# Schematic.net
KiCad netlist of a schematic drawn in Altium Designer
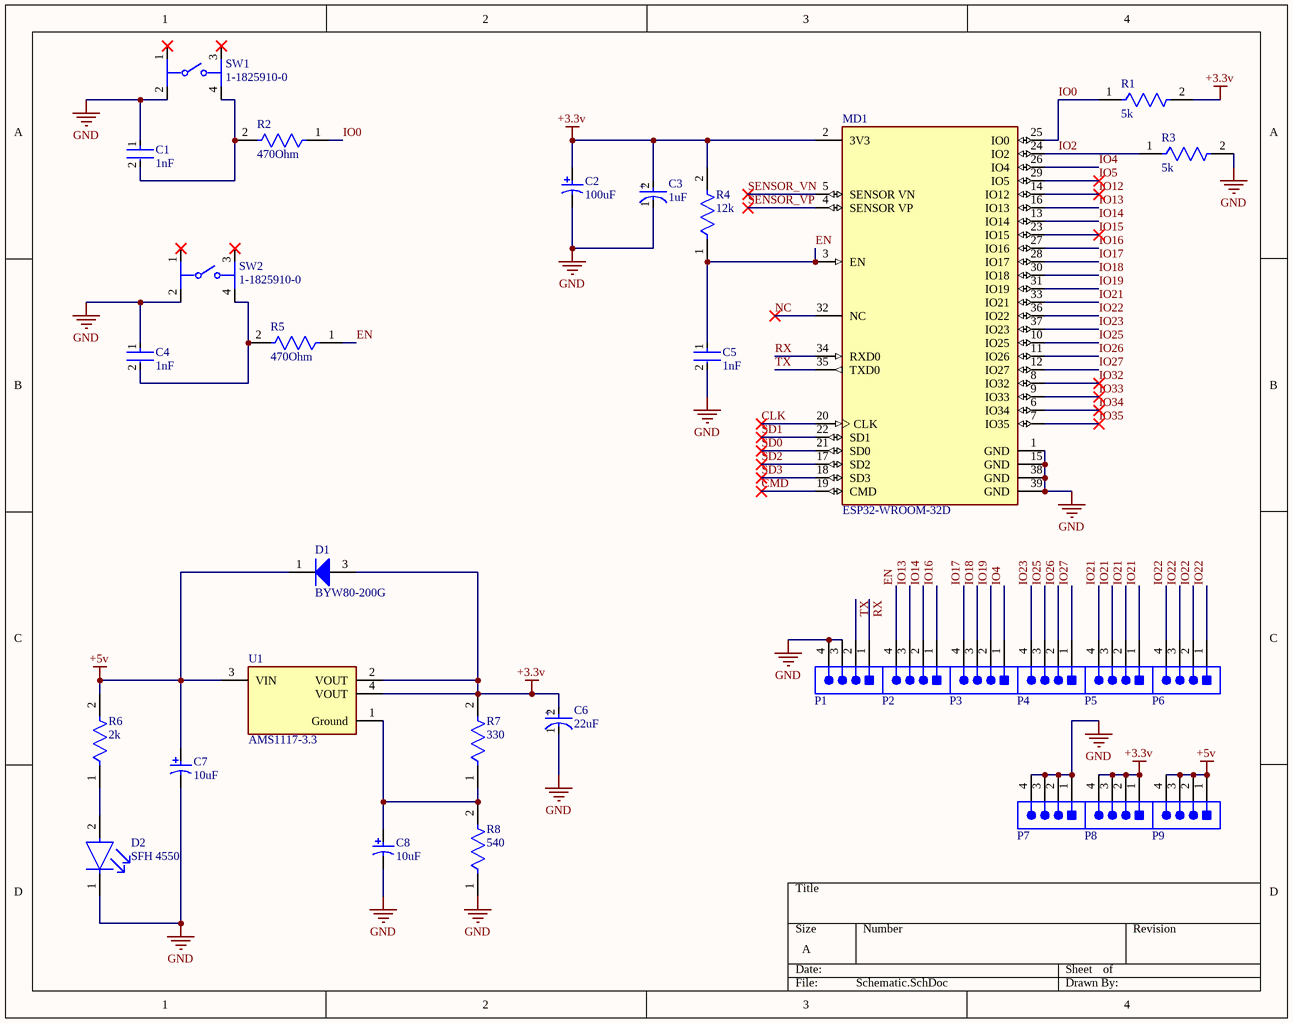
[diagram p0: Schematic.SchDoc]

(export (version "E")
  (design (tool "Eeschema 10.0.6"))
  (components
    (comp (ref "C1")
      (value "1nF")
      (footprint "FP-VY2102M29Y5US6TV7-MFG")
      (fields (field (name "VOLTAGE") "300V") (field (name "TOLERANCE") "20%"))
      (libsource (lib "Altium Content Vault") (part "11868f565c42a9108669ba33697ecf6"))
    )
    (comp (ref "C2")
      (value "100uF")
      (footprint "NIC-RNS-8x11.5-2_V")
      (description "Aluminum Electrolytic Capacitor, 100 uF +/-20%, 10 V, -55 to 105 degC, 2-Pin THD, RoHS")
      (fields (field (name "PARTNUMBER") "RNS1A101MDN1KX") (field (name "MANUFACTURER") "Nichicon"))
      (libsource (lib "Altium Content Vault") (part "NIC-CAP-P-2"))
    )
    (comp (ref "C3")
      (value "1uF")
      (footprint "FP-ECA-2WHG010-MFG")
      (description "ECA-2WHG010 Aluminum Electrolytic Capacitor, 1 uF, 450 V, ± 20%, 2000 hours @ 105°C, Radial Leaded")
      (fields (field (name "TOLERANCE") "20%") (field (name "VOLTAGE") "450V"))
      (libsource (lib "Altium Content Vault") (part "a00bbbee19879c290e62620ae7e47b1"))
    )
    (comp (ref "C4")
      (value "1nF")
      (footprint "FP-VY2102M29Y5US6TV7-MFG")
      (fields (field (name "VOLTAGE") "300V") (field (name "TOLERANCE") "20%"))
      (libsource (lib "Altium Content Vault") (part "11868f565c42a9108669ba33697ecf6"))
    )
    (comp (ref "C5")
      (value "1nF")
      (footprint "FP-VY2102M29Y5US6TV7-MFG")
      (fields (field (name "VOLTAGE") "300V") (field (name "TOLERANCE") "20%"))
      (libsource (lib "Altium Content Vault") (part "11868f565c42a9108669ba33697ecf6"))
    )
    (comp (ref "C6")
      (value "22uF")
      (footprint "FP-RAD-TH-D_16_0_5-L_20_2-MFG")
      (description "Aluminum Electrolytic Capacitors (Radial Lead Type) 22uF ±20% 450V")
      (fields (field (name "TOLERANCE") "20%") (field (name "VOLTAGE") "450V"))
      (libsource (lib "Altium Content Vault") (part "203bc49f2ac43e59fd269a8c329ed05"))
    )
    (comp (ref "C7")
      (value "10uF")
      (footprint "NIC-RNS-8x11.5-2_V")
      (description "Aluminum Electrolytic Capacitor, 100 uF +/-20%, 10 V, -55 to 105 degC, 2-Pin THD, RoHS")
      (fields (field (name "PARTNUMBER") "RNS1A101MDN1KX") (field (name "MANUFACTURER") "Nichicon"))
      (libsource (lib "Altium Content Vault") (part "NIC-CAP-P-2"))
    )
    (comp (ref "C8")
      (value "10uF")
      (footprint "NIC-RNS-8x11.5-2_V")
      (description "Aluminum Electrolytic Capacitor, 100 uF +/-20%, 10 V, -55 to 105 degC, 2-Pin THD, RoHS")
      (fields (field (name "PARTNUMBER") "RNS1A101MDN1KX") (field (name "MANUFACTURER") "Nichicon"))
      (libsource (lib "Altium Content Vault") (part "NIC-CAP-P-2"))
    )
    (comp (ref "D1")
      (value "BYW80-200G")
      (footprint "ONSC-TO-220-2-221B-04_E")
      (description "SWITCHMODE(TM) Power Rectifier, 2-Pin TO-220, Pb-Free, Tube")
      (fields (field (name "MANUFACTURER") "On Semiconductor"))
      (libsource (lib "Altium Content Vault") (part "ONSC-D-K1A3-2_A"))
    )
    (comp (ref "D2")
      (value "SFH 4550")
      (footprint "FP-SFH_4550-MFG")
      (description "EMITTER IR 860NM 100MA RADIAL")
      (fields
        (field (name "OCTOPART") "https://octopart.com/sfh+4550-osram+opto-55410894")
        (field (name "MANUFACTURER") "Osram Opto")
      )
      (libsource (lib "Altium Content Vault") (part "75a0115997dd6a71327e26aab64f6f8"))
    )
    (comp (ref "MD1")
      (value "ESP32-WROOM-32D")
      (footprint "FP-ESP32-WROOM-32D-MFG")
      (description "WIFI MODULE 32MBITS SPI FLASH")
      (fields
        (field (name "OCTOPART") "https://octopart.com/esp32-wroom-32d-espressif+systems-91040050")
        (field (name "MANUFACTURER") "Espressif Systems")
      )
      (libsource (lib "Altium Content Vault") (part "a031a76f8c27026a7a7f4657ff233a3"))
    )
    (comp (ref "P1")
      (value "B4B-EH-A(LF)(SN)")
      (footprint "JST-B4B-EH-A_V")
      (fields (field (name "MANUFACTURER") "JST"))
      (libsource (lib "Altium Content Vault") (part "CN-1P-M-R4"))
    )
    (comp (ref "P2")
      (value "B4B-EH-A(LF)(SN)")
      (footprint "JST-B4B-EH-A_V")
      (fields (field (name "MANUFACTURER") "JST"))
      (libsource (lib "Altium Content Vault") (part "CN-1P-M-R4"))
    )
    (comp (ref "P3")
      (value "B4B-EH-A(LF)(SN)")
      (footprint "JST-B4B-EH-A_V")
      (fields (field (name "MANUFACTURER") "JST"))
      (libsource (lib "Altium Content Vault") (part "CN-1P-M-R4"))
    )
    (comp (ref "P4")
      (value "B4B-EH-A(LF)(SN)")
      (footprint "JST-B4B-EH-A_V")
      (fields (field (name "MANUFACTURER") "JST"))
      (libsource (lib "Altium Content Vault") (part "CN-1P-M-R4"))
    )
    (comp (ref "P5")
      (value "B4B-EH-A(LF)(SN)")
      (footprint "JST-B4B-EH-A_V")
      (fields (field (name "MANUFACTURER") "JST"))
      (libsource (lib "Altium Content Vault") (part "CN-1P-M-R4"))
    )
    (comp (ref "P6")
      (value "B4B-EH-A(LF)(SN)")
      (footprint "JST-B4B-EH-A_V")
      (fields (field (name "MANUFACTURER") "JST"))
      (libsource (lib "Altium Content Vault") (part "CN-1P-M-R4"))
    )
    (comp (ref "P7")
      (value "B4B-EH-A(LF)(SN)")
      (footprint "JST-B4B-EH-A_V")
      (fields (field (name "MANUFACTURER") "JST"))
      (libsource (lib "Altium Content Vault") (part "CN-1P-M-R4"))
    )
    (comp (ref "P8")
      (value "B4B-EH-A(LF)(SN)")
      (footprint "JST-B4B-EH-A_V")
      (fields (field (name "MANUFACTURER") "JST"))
      (libsource (lib "Altium Content Vault") (part "CN-1P-M-R4"))
    )
    (comp (ref "P9")
      (value "B4B-EH-A(LF)(SN)")
      (footprint "JST-B4B-EH-A_V")
      (fields (field (name "MANUFACTURER") "JST"))
      (libsource (lib "Altium Content Vault") (part "CN-1P-M-R4"))
    )
    (comp (ref "R1")
      (value "5k")
      (footprint "FP-MRS1600-MFG")
      (description "RES 20K OHM 0.4W 1% AXIAL")
      (fields (field (name "TOLERANCE") "1%"))
      (libsource (lib "Altium Content Vault") (part "1029c3af85768c4190bb7ad29bc67b5"))
    )
    (comp (ref "R2")
      (value "470Ohm")
      (footprint "FP-MRS1600-MFG")
      (description "RES 20K OHM 0.4W 1% AXIAL")
      (fields (field (name "TOLERANCE") "1%"))
      (libsource (lib "Altium Content Vault") (part "1029c3af85768c4190bb7ad29bc67b5"))
    )
    (comp (ref "R3")
      (value "5k")
      (footprint "FP-MRS1600-MFG")
      (description "RES 20K OHM 0.4W 1% AXIAL")
      (fields (field (name "TOLERANCE") "1%"))
      (libsource (lib "Altium Content Vault") (part "1029c3af85768c4190bb7ad29bc67b5"))
    )
    (comp (ref "R4")
      (value "12k")
      (footprint "FP-MRS1600-MFG")
      (description "RES 20K OHM 0.4W 1% AXIAL")
      (fields (field (name "TOLERANCE") "1%"))
      (libsource (lib "Altium Content Vault") (part "1029c3af85768c4190bb7ad29bc67b5"))
    )
    (comp (ref "R5")
      (value "470Ohm")
      (footprint "FP-MRS1600-MFG")
      (description "RES 20K OHM 0.4W 1% AXIAL")
      (fields (field (name "TOLERANCE") "1%"))
      (libsource (lib "Altium Content Vault") (part "1029c3af85768c4190bb7ad29bc67b5"))
    )
    (comp (ref "R6")
      (value "2k")
      (footprint "FP-MRS1600-MFG")
      (description "RES 20K OHM 0.4W 1% AXIAL")
      (fields (field (name "TOLERANCE") "1%"))
      (libsource (lib "Altium Content Vault") (part "1029c3af85768c4190bb7ad29bc67b5"))
    )
    (comp (ref "R7")
      (value "330")
      (footprint "FP-MRS1600-MFG")
      (description "RES 20K OHM 0.4W 1% AXIAL")
      (fields (field (name "TOLERANCE") "1%"))
      (libsource (lib "Altium Content Vault") (part "1029c3af85768c4190bb7ad29bc67b5"))
    )
    (comp (ref "R8")
      (value "540")
      (footprint "FP-MRS1600-MFG")
      (description "RES 20K OHM 0.4W 1% AXIAL")
      (fields (field (name "TOLERANCE") "1%"))
      (libsource (lib "Altium Content Vault") (part "1029c3af85768c4190bb7ad29bc67b5"))
    )
    (comp (ref "SW1")
      (value "1-1825910-0")
      (footprint "FP-1-1825910-0-MFG")
      (description "SWITCH TACTILE SPST-NO 0.05A 24V")
      (libsource (lib "Altium Content Vault") (part "b8895f3f4cefb76e1819d2863dba89b"))
    )
    (comp (ref "SW2")
      (value "1-1825910-0")
      (footprint "FP-1-1825910-0-MFG")
      (description "SWITCH TACTILE SPST-NO 0.05A 24V")
      (libsource (lib "Altium Content Vault") (part "b8895f3f4cefb76e1819d2863dba89b"))
    )
    (comp (ref "U1")
      (value "AMS1117-3.3")
      (footprint "FP-AMS1117-IPC_C")
      (description "LDO Voltage Regulators 1A, 3.3V")
      (fields
        (field (name "OCTOPART") "https://octopart.com/ams1117-3.3-advanced+monolithic+systems-25899300")
        (field (name "MANUFACTURER") "Advanced Monolithic Systems")
      )
      (libsource (lib "Altium Content Vault") (part "8bdbb5f8e77002000e30dd2845d0354"))
    )
  )
  (nets
    (net (code "1") (name "+3.3v") (class "Default")
      (node (ref "C2") (pin "1") (pinfunction "1_1") (pintype "passive"))
      (node (ref "C3") (pin "2") (pinfunction "A_2") (pintype "passive"))
      (node (ref "C6") (pin "2") (pinfunction "A_2") (pintype "passive"))
      (node (ref "D1") (pin "3") (pinfunction "A_3") (pintype "passive"))
      (node (ref "MD1") (pin "2") (pinfunction "3V3_2") (pintype "power_in"))
      (node (ref "P8") (pin "1") (pinfunction "1_1") (pintype "passive"))
      (node (ref "P8") (pin "2") (pinfunction "2_2") (pintype "passive"))
      (node (ref "P8") (pin "3") (pinfunction "3_3") (pintype "passive"))
      (node (ref "P8") (pin "4") (pinfunction "4_4") (pintype "passive"))
      (node (ref "R1") (pin "2") (pinfunction "2_2") (pintype "passive"))
      (node (ref "R4") (pin "2") (pinfunction "2_2") (pintype "passive"))
      (node (ref "R7") (pin "2") (pinfunction "2_2") (pintype "passive"))
      (node (ref "U1") (pin "2") (pinfunction "VOUT_2") (pintype "passive"))
      (node (ref "U1") (pin "4") (pinfunction "VOUT_4") (pintype "passive"))
    )
    (net (code "2") (name "+5v") (class "Default")
      (node (ref "C7") (pin "1") (pinfunction "1_1") (pintype "passive"))
      (node (ref "D1") (pin "1") (pinfunction "K_1") (pintype "passive"))
      (node (ref "P9") (pin "1") (pinfunction "1_1") (pintype "passive"))
      (node (ref "P9") (pin "2") (pinfunction "2_2") (pintype "passive"))
      (node (ref "P9") (pin "3") (pinfunction "3_3") (pintype "passive"))
      (node (ref "P9") (pin "4") (pinfunction "4_4") (pintype "passive"))
      (node (ref "R6") (pin "2") (pinfunction "2_2") (pintype "passive"))
      (node (ref "U1") (pin "3") (pinfunction "VIN_3") (pintype "power_in"))
    )
    (net (code "3") (name "/CLK") (class "Default")
      (node (ref "MD1") (pin "20") (pinfunction "CLK_20") (pintype "input+no_connect"))
    )
    (net (code "4") (name "/CMD") (class "Default")
      (node (ref "MD1") (pin "19") (pinfunction "CMD_19") (pintype "bidirectional+no_connect"))
    )
    (net (code "5") (name "/EN") (class "Default")
      (node (ref "C5") (pin "1") (pinfunction "1_1") (pintype "passive"))
      (node (ref "MD1") (pin "3") (pinfunction "EN_3") (pintype "input"))
      (node (ref "P2") (pin "4") (pinfunction "4_4") (pintype "passive"))
      (node (ref "R4") (pin "1") (pinfunction "1_1") (pintype "passive"))
      (node (ref "R5") (pin "1") (pinfunction "1_1") (pintype "passive"))
    )
    (net (code "6") (name "/IO0") (class "Default")
      (node (ref "MD1") (pin "25") (pinfunction "IO0_25") (pintype "bidirectional"))
      (node (ref "R1") (pin "1") (pinfunction "1_1") (pintype "passive"))
      (node (ref "R2") (pin "1") (pinfunction "1_1") (pintype "passive"))
    )
    (net (code "7") (name "/IO2") (class "Default")
      (node (ref "MD1") (pin "24") (pinfunction "IO2_24") (pintype "bidirectional"))
      (node (ref "R3") (pin "1") (pinfunction "1_1") (pintype "passive"))
    )
    (net (code "8") (name "/IO4") (class "Default")
      (node (ref "MD1") (pin "26") (pinfunction "IO4_26") (pintype "bidirectional"))
      (node (ref "P3") (pin "1") (pinfunction "1_1") (pintype "passive"))
    )
    (net (code "9") (name "/IO5") (class "Default")
      (node (ref "MD1") (pin "29") (pinfunction "IO5_29") (pintype "bidirectional+no_connect"))
    )
    (net (code "10") (name "/IO12") (class "Default")
      (node (ref "MD1") (pin "14") (pinfunction "IO12_14") (pintype "bidirectional+no_connect"))
    )
    (net (code "11") (name "/IO13") (class "Default")
      (node (ref "MD1") (pin "16") (pinfunction "IO13_16") (pintype "bidirectional"))
      (node (ref "P2") (pin "3") (pinfunction "3_3") (pintype "passive"))
    )
    (net (code "12") (name "/IO14") (class "Default")
      (node (ref "MD1") (pin "13") (pinfunction "IO14_13") (pintype "bidirectional"))
      (node (ref "P2") (pin "2") (pinfunction "2_2") (pintype "passive"))
    )
    (net (code "13") (name "/IO15") (class "Default")
      (node (ref "MD1") (pin "23") (pinfunction "IO15_23") (pintype "bidirectional+no_connect"))
    )
    (net (code "14") (name "/IO16") (class "Default")
      (node (ref "MD1") (pin "27") (pinfunction "IO16_27") (pintype "bidirectional"))
      (node (ref "P2") (pin "1") (pinfunction "1_1") (pintype "passive"))
    )
    (net (code "15") (name "/IO17") (class "Default")
      (node (ref "MD1") (pin "28") (pinfunction "IO17_28") (pintype "bidirectional"))
      (node (ref "P3") (pin "4") (pinfunction "4_4") (pintype "passive"))
    )
    (net (code "16") (name "/IO18") (class "Default")
      (node (ref "MD1") (pin "30") (pinfunction "IO18_30") (pintype "bidirectional"))
      (node (ref "P3") (pin "3") (pinfunction "3_3") (pintype "passive"))
    )
    (net (code "17") (name "/IO19") (class "Default")
      (node (ref "MD1") (pin "31") (pinfunction "IO19_31") (pintype "bidirectional"))
      (node (ref "P3") (pin "2") (pinfunction "2_2") (pintype "passive"))
    )
    (net (code "18") (name "/IO21") (class "Default")
      (node (ref "MD1") (pin "33") (pinfunction "IO21_33") (pintype "bidirectional"))
      (node (ref "P5") (pin "1") (pinfunction "1_1") (pintype "passive"))
      (node (ref "P5") (pin "2") (pinfunction "2_2") (pintype "passive"))
      (node (ref "P5") (pin "3") (pinfunction "3_3") (pintype "passive"))
      (node (ref "P5") (pin "4") (pinfunction "4_4") (pintype "passive"))
    )
    (net (code "19") (name "/IO22") (class "Default")
      (node (ref "MD1") (pin "36") (pinfunction "IO22_36") (pintype "bidirectional"))
      (node (ref "P6") (pin "1") (pinfunction "1_1") (pintype "passive"))
      (node (ref "P6") (pin "2") (pinfunction "2_2") (pintype "passive"))
      (node (ref "P6") (pin "3") (pinfunction "3_3") (pintype "passive"))
      (node (ref "P6") (pin "4") (pinfunction "4_4") (pintype "passive"))
    )
    (net (code "20") (name "/IO23") (class "Default")
      (node (ref "MD1") (pin "37") (pinfunction "IO23_37") (pintype "bidirectional"))
      (node (ref "P4") (pin "4") (pinfunction "4_4") (pintype "passive"))
    )
    (net (code "21") (name "/IO25") (class "Default")
      (node (ref "MD1") (pin "10") (pinfunction "IO25_10") (pintype "bidirectional"))
      (node (ref "P4") (pin "3") (pinfunction "3_3") (pintype "passive"))
    )
    (net (code "22") (name "/IO26") (class "Default")
      (node (ref "MD1") (pin "11") (pinfunction "IO26_11") (pintype "bidirectional"))
      (node (ref "P4") (pin "2") (pinfunction "2_2") (pintype "passive"))
    )
    (net (code "23") (name "/IO27") (class "Default")
      (node (ref "MD1") (pin "12") (pinfunction "IO27_12") (pintype "bidirectional"))
      (node (ref "P4") (pin "1") (pinfunction "1_1") (pintype "passive"))
    )
    (net (code "24") (name "/IO32") (class "Default")
      (node (ref "MD1") (pin "8") (pinfunction "IO32_8") (pintype "bidirectional+no_connect"))
    )
    (net (code "25") (name "/IO33") (class "Default")
      (node (ref "MD1") (pin "9") (pinfunction "IO33_9") (pintype "bidirectional+no_connect"))
    )
    (net (code "26") (name "/IO34") (class "Default")
      (node (ref "MD1") (pin "6") (pinfunction "IO34_6") (pintype "bidirectional+no_connect"))
    )
    (net (code "27") (name "/IO35") (class "Default")
      (node (ref "MD1") (pin "7") (pinfunction "IO35_7") (pintype "bidirectional+no_connect"))
    )
    (net (code "28") (name "/NC") (class "Default")
      (node (ref "MD1") (pin "32") (pinfunction "NC_32") (pintype "passive+no_connect"))
    )
    (net (code "29") (name "/RX") (class "Default")
      (node (ref "MD1") (pin "34") (pinfunction "RXD0_34") (pintype "input"))
      (node (ref "P1") (pin "1") (pinfunction "1_1") (pintype "passive"))
    )
    (net (code "30") (name "/SD0") (class "Default")
      (node (ref "MD1") (pin "21") (pinfunction "SD0_21") (pintype "bidirectional+no_connect"))
    )
    (net (code "31") (name "/SD1") (class "Default")
      (node (ref "MD1") (pin "22") (pinfunction "SD1_22") (pintype "bidirectional+no_connect"))
    )
    (net (code "32") (name "/SD2") (class "Default")
      (node (ref "MD1") (pin "17") (pinfunction "SD2_17") (pintype "bidirectional+no_connect"))
    )
    (net (code "33") (name "/SD3") (class "Default")
      (node (ref "MD1") (pin "18") (pinfunction "SD3_18") (pintype "bidirectional+no_connect"))
    )
    (net (code "34") (name "/SENSOR_VN") (class "Default")
      (node (ref "MD1") (pin "5") (pinfunction "SENSOR_VN_5") (pintype "bidirectional+no_connect"))
    )
    (net (code "35") (name "/SENSOR_VP") (class "Default")
      (node (ref "MD1") (pin "4") (pinfunction "SENSOR_VP_4") (pintype "bidirectional+no_connect"))
    )
    (net (code "36") (name "/TX") (class "Default")
      (node (ref "MD1") (pin "35") (pinfunction "TXD0_35") (pintype "output"))
      (node (ref "P1") (pin "2") (pinfunction "2_2") (pintype "passive"))
    )
    (net (code "37") (name "GND") (class "Default")
      (node (ref "C1") (pin "1") (pinfunction "1_1") (pintype "passive"))
      (node (ref "C2") (pin "2") (pinfunction "2_2") (pintype "passive"))
      (node (ref "C3") (pin "1") (pinfunction "C_1") (pintype "passive"))
      (node (ref "C4") (pin "1") (pinfunction "1_1") (pintype "passive"))
      (node (ref "C5") (pin "2") (pinfunction "2_2") (pintype "passive"))
      (node (ref "C6") (pin "1") (pinfunction "C_1") (pintype "passive"))
      (node (ref "C7") (pin "2") (pinfunction "2_2") (pintype "passive"))
      (node (ref "C8") (pin "2") (pinfunction "2_2") (pintype "passive"))
      (node (ref "D2") (pin "1") (pinfunction "C_1") (pintype "passive"))
      (node (ref "MD1") (pin "1") (pinfunction "GND_1") (pintype "power_in"))
      (node (ref "MD1") (pin "15") (pinfunction "GND_15") (pintype "power_in"))
      (node (ref "MD1") (pin "38") (pinfunction "GND_38") (pintype "power_in"))
      (node (ref "MD1") (pin "39") (pinfunction "GND_39") (pintype "power_in"))
      (node (ref "P1") (pin "3") (pinfunction "3_3") (pintype "passive"))
      (node (ref "P1") (pin "4") (pinfunction "4_4") (pintype "passive"))
      (node (ref "P7") (pin "1") (pinfunction "1_1") (pintype "passive"))
      (node (ref "P7") (pin "2") (pinfunction "2_2") (pintype "passive"))
      (node (ref "P7") (pin "3") (pinfunction "3_3") (pintype "passive"))
      (node (ref "P7") (pin "4") (pinfunction "4_4") (pintype "passive"))
      (node (ref "R3") (pin "2") (pinfunction "2_2") (pintype "passive"))
      (node (ref "R8") (pin "1") (pinfunction "1_1") (pintype "passive"))
      (node (ref "SW1") (pin "2") (pinfunction "2_2") (pintype "passive"))
      (node (ref "SW2") (pin "2") (pinfunction "2_2") (pintype "passive"))
    )
    (net (code "38") (name "Net-(C1-Pad2)") (class "Default")
      (node (ref "C1") (pin "2") (pinfunction "2_2") (pintype "passive"))
      (node (ref "R2") (pin "2") (pinfunction "2_2") (pintype "passive"))
      (node (ref "SW1") (pin "4") (pinfunction "4_4") (pintype "passive"))
    )
    (net (code "39") (name "Net-(C4-Pad2)") (class "Default")
      (node (ref "C4") (pin "2") (pinfunction "2_2") (pintype "passive"))
      (node (ref "R5") (pin "2") (pinfunction "2_2") (pintype "passive"))
      (node (ref "SW2") (pin "4") (pinfunction "4_4") (pintype "passive"))
    )
    (net (code "40") (name "Net-(D2-A)") (class "Default")
      (node (ref "D2") (pin "2") (pinfunction "A_2") (pintype "passive"))
      (node (ref "R6") (pin "1") (pinfunction "1_1") (pintype "passive"))
    )
    (net (code "41") (name "Net-(U1-Ground)") (class "Default")
      (node (ref "C8") (pin "1") (pinfunction "1_1") (pintype "passive"))
      (node (ref "R7") (pin "1") (pinfunction "1_1") (pintype "passive"))
      (node (ref "R8") (pin "2") (pinfunction "2_2") (pintype "passive"))
      (node (ref "U1") (pin "1") (pinfunction "Ground_1") (pintype "power_in"))
    )
    (net (code "42") (name "unconnected-(SW1-Pad1)") (class "Default")
      (node (ref "SW1") (pin "1") (pinfunction "1_1") (pintype "passive+no_connect"))
    )
    (net (code "43") (name "unconnected-(SW1-Pad3)") (class "Default")
      (node (ref "SW1") (pin "3") (pinfunction "3_3") (pintype "passive+no_connect"))
    )
    (net (code "44") (name "unconnected-(SW2-Pad1)") (class "Default")
      (node (ref "SW2") (pin "1") (pinfunction "1_1") (pintype "passive+no_connect"))
    )
    (net (code "45") (name "unconnected-(SW2-Pad3)") (class "Default")
      (node (ref "SW2") (pin "3") (pinfunction "3_3") (pintype "passive+no_connect"))
    )
  )
)
